# buffNlvlshifter2.net
KiCad netlist of a schematic drawn in Altium Designer
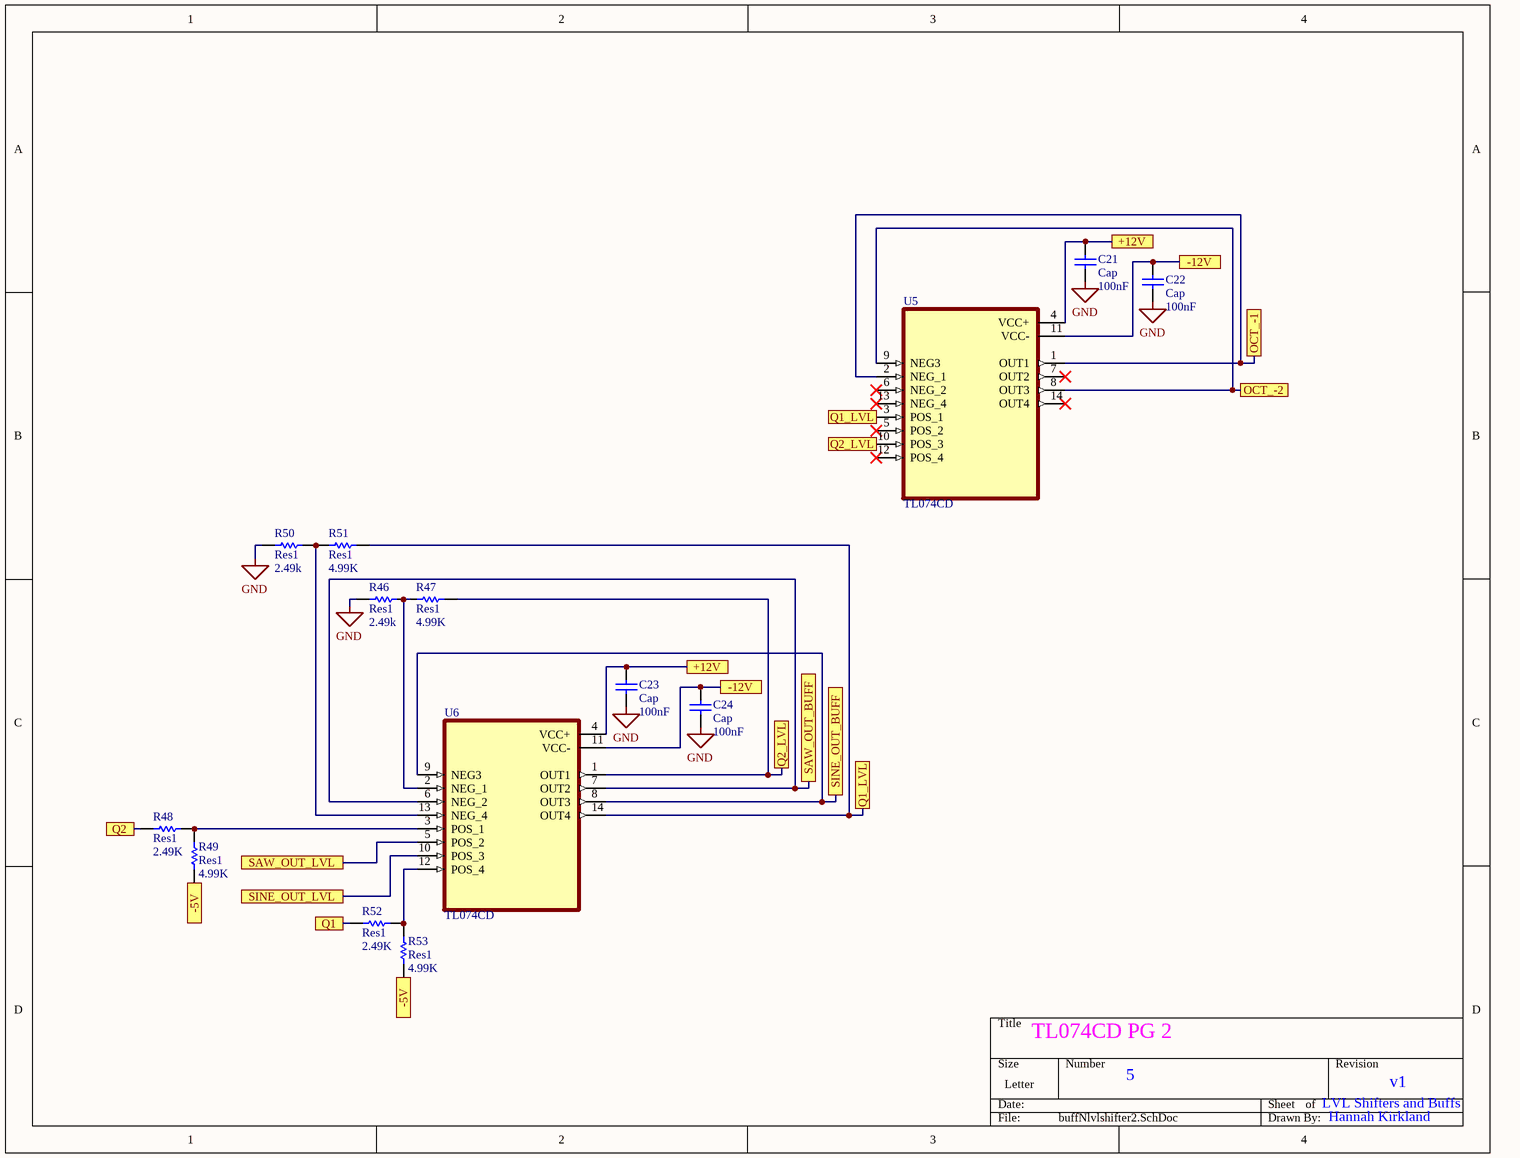
[diagram p0: buffNlvlshifter2.SchDoc]

(export (version "E")
  (design (tool "Eeschema 10.0.6"))
  (components
    (comp (ref "C21")
      (value "Cap")
      (footprint "C1206")
      (description "Capacitor")
      (fields (field (name "ALTIUM_VALUE") "100nF") (field (name "PUBLISHER") "Altium Limited"))
      (libsource (lib "Miscellaneous Devices") (part "Cap"))
    )
    (comp (ref "C22")
      (value "Cap")
      (footprint "C1206")
      (description "Capacitor")
      (fields (field (name "ALTIUM_VALUE") "100nF") (field (name "PUBLISHER") "Altium Limited"))
      (libsource (lib "Miscellaneous Devices") (part "Cap"))
    )
    (comp (ref "C23")
      (value "Cap")
      (footprint "C1206")
      (description "Capacitor")
      (fields (field (name "ALTIUM_VALUE") "100nF") (field (name "PUBLISHER") "Altium Limited"))
      (libsource (lib "Miscellaneous Devices") (part "Cap"))
    )
    (comp (ref "C24")
      (value "Cap")
      (footprint "C1206")
      (description "Capacitor")
      (fields (field (name "ALTIUM_VALUE") "100nF") (field (name "PUBLISHER") "Altium Limited"))
      (libsource (lib "Miscellaneous Devices") (part "Cap"))
    )
    (comp (ref "R46")
      (value "Res1")
      (footprint "C1206")
      (description "Resistor")
      (fields (field (name "ALTIUM_VALUE") "2.49k") (field (name "PUBLISHER") "Altium Limited"))
      (libsource (lib "Miscellaneous Devices") (part "Res1"))
    )
    (comp (ref "R47")
      (value "Res1")
      (footprint "C1206")
      (description "Resistor")
      (fields (field (name "ALTIUM_VALUE") "4.99K") (field (name "PUBLISHER") "Altium Limited"))
      (libsource (lib "Miscellaneous Devices") (part "Res1"))
    )
    (comp (ref "R48")
      (value "Res1")
      (footprint "C1206")
      (description "Resistor")
      (fields (field (name "ALTIUM_VALUE") "2.49K") (field (name "PUBLISHER") "Altium Limited"))
      (libsource (lib "Miscellaneous Devices") (part "Res1"))
    )
    (comp (ref "R49")
      (value "Res1")
      (footprint "C1206")
      (description "Resistor")
      (fields (field (name "ALTIUM_VALUE") "4.99K") (field (name "PUBLISHER") "Altium Limited"))
      (libsource (lib "Miscellaneous Devices") (part "Res1"))
    )
    (comp (ref "R50")
      (value "Res1")
      (footprint "C1206")
      (description "Resistor")
      (fields (field (name "ALTIUM_VALUE") "2.49k") (field (name "PUBLISHER") "Altium Limited"))
      (libsource (lib "Miscellaneous Devices") (part "Res1"))
    )
    (comp (ref "R51")
      (value "Res1")
      (footprint "C1206")
      (description "Resistor")
      (fields (field (name "ALTIUM_VALUE") "4.99K") (field (name "PUBLISHER") "Altium Limited"))
      (libsource (lib "Miscellaneous Devices") (part "Res1"))
    )
    (comp (ref "R52")
      (value "Res1")
      (footprint "C1206")
      (description "Resistor")
      (fields (field (name "ALTIUM_VALUE") "2.49K") (field (name "PUBLISHER") "Altium Limited"))
      (libsource (lib "Miscellaneous Devices") (part "Res1"))
    )
    (comp (ref "R53")
      (value "Res1")
      (footprint "C1206")
      (description "Resistor")
      (fields (field (name "ALTIUM_VALUE") "4.99K") (field (name "PUBLISHER") "Altium Limited"))
      (libsource (lib "Miscellaneous Devices") (part "Res1"))
    )
    (comp (ref "U5")
      (value "TL074CD")
      (footprint "SOIC127P600X175-14N")
      (description "Quad Low-Noise JFET-Input General-Purpose Operational Amplifier 14-SOIC 0 to 70")
      (fields
        (field (name "MF") "Texas Instruments")
        (field (name "BUYPART") "https://www.snapeda.com/parts/TL074CD/Texas%20Instruments/view-part/4793449/?ref=eda")
      )
      (libsource (lib "TL074CD") (part "TL074CD"))
    )
    (comp (ref "U6")
      (value "TL074CD")
      (footprint "SOIC127P600X175-14N")
      (description "Quad Low-Noise JFET-Input General-Purpose Operational Amplifier 14-SOIC 0 to 70")
      (fields
        (field (name "MF") "Texas Instruments")
        (field (name "BUYPART") "https://www.snapeda.com/parts/TL074CD/Texas%20Instruments/view-part/4793449/?ref=eda")
      )
      (libsource (lib "TL074CD") (part "TL074CD"))
    )
  )
  (nets
    (net (code "1") (name "/+12V") (class "Default")
      (node (ref "C21") (pin "2") (pinfunction "2_2") (pintype "passive"))
      (node (ref "C23") (pin "2") (pinfunction "2_2") (pintype "passive"))
      (node (ref "U5") (pin "4") (pinfunction "VCC+_4") (pintype "power_in"))
      (node (ref "U6") (pin "4") (pinfunction "VCC+_4") (pintype "power_in"))
    )
    (net (code "2") (name "/-5V") (class "Default")
      (node (ref "R49") (pin "1") (pinfunction "1_1") (pintype "passive"))
      (node (ref "R53") (pin "1") (pinfunction "1_1") (pintype "passive"))
    )
    (net (code "3") (name "/-12V") (class "Default")
      (node (ref "C22") (pin "2") (pinfunction "2_2") (pintype "passive"))
      (node (ref "C24") (pin "2") (pinfunction "2_2") (pintype "passive"))
      (node (ref "U5") (pin "11") (pinfunction "VCC-_11") (pintype "power_in"))
      (node (ref "U6") (pin "11") (pinfunction "VCC-_11") (pintype "power_in"))
    )
    (net (code "4") (name "/OCT_-1") (class "Default")
      (node (ref "U5") (pin "1") (pinfunction "OUT1_1") (pintype "output"))
      (node (ref "U5") (pin "2") (pinfunction "NEG_1_2") (pintype "input"))
    )
    (net (code "5") (name "/OCT_-2") (class "Default")
      (node (ref "U5") (pin "8") (pinfunction "OUT3_8") (pintype "output"))
      (node (ref "U5") (pin "9") (pinfunction "NEG3_9") (pintype "input"))
    )
    (net (code "6") (name "/Q1") (class "Default")
      (node (ref "R52") (pin "1") (pinfunction "1_1") (pintype "passive"))
    )
    (net (code "7") (name "/Q1_LVL") (class "Default")
      (node (ref "R51") (pin "2") (pinfunction "2_2") (pintype "passive"))
      (node (ref "U5") (pin "3") (pinfunction "POS_1_3") (pintype "input"))
      (node (ref "U6") (pin "14") (pinfunction "OUT4_14") (pintype "output"))
    )
    (net (code "8") (name "/Q2") (class "Default")
      (node (ref "R48") (pin "1") (pinfunction "1_1") (pintype "passive"))
    )
    (net (code "9") (name "/Q2_LVL") (class "Default")
      (node (ref "R47") (pin "2") (pinfunction "2_2") (pintype "passive"))
      (node (ref "U5") (pin "10") (pinfunction "POS_3_10") (pintype "input"))
      (node (ref "U6") (pin "1") (pinfunction "OUT1_1") (pintype "output"))
    )
    (net (code "10") (name "/SAW_OUT_BUFF") (class "Default")
      (node (ref "U6") (pin "6") (pinfunction "NEG_2_6") (pintype "input"))
      (node (ref "U6") (pin "7") (pinfunction "OUT2_7") (pintype "output"))
    )
    (net (code "11") (name "/SAW_OUT_LVL") (class "Default")
      (node (ref "U6") (pin "5") (pinfunction "POS_2_5") (pintype "input"))
    )
    (net (code "12") (name "/SINE_OUT_BUFF") (class "Default")
      (node (ref "U6") (pin "8") (pinfunction "OUT3_8") (pintype "output"))
      (node (ref "U6") (pin "9") (pinfunction "NEG3_9") (pintype "input"))
    )
    (net (code "13") (name "/SINE_OUT_LVL") (class "Default")
      (node (ref "U6") (pin "10") (pinfunction "POS_3_10") (pintype "input"))
    )
    (net (code "14") (name "GND") (class "Default")
      (node (ref "C21") (pin "1") (pinfunction "1_1") (pintype "passive"))
      (node (ref "C22") (pin "1") (pinfunction "1_1") (pintype "passive"))
      (node (ref "C23") (pin "1") (pinfunction "1_1") (pintype "passive"))
      (node (ref "C24") (pin "1") (pinfunction "1_1") (pintype "passive"))
      (node (ref "R46") (pin "1") (pinfunction "1_1") (pintype "passive"))
      (node (ref "R50") (pin "1") (pinfunction "1_1") (pintype "passive"))
    )
    (net (code "15") (name "Net-(U6-NEG_1)") (class "Default")
      (node (ref "R46") (pin "2") (pinfunction "2_2") (pintype "passive"))
      (node (ref "R47") (pin "1") (pinfunction "1_1") (pintype "passive"))
      (node (ref "U6") (pin "2") (pinfunction "NEG_1_2") (pintype "input"))
    )
    (net (code "16") (name "Net-(U6-NEG_4)") (class "Default")
      (node (ref "R50") (pin "2") (pinfunction "2_2") (pintype "passive"))
      (node (ref "R51") (pin "1") (pinfunction "1_1") (pintype "passive"))
      (node (ref "U6") (pin "13") (pinfunction "NEG_4_13") (pintype "input"))
    )
    (net (code "17") (name "Net-(U6-POS_1)") (class "Default")
      (node (ref "R48") (pin "2") (pinfunction "2_2") (pintype "passive"))
      (node (ref "R49") (pin "2") (pinfunction "2_2") (pintype "passive"))
      (node (ref "U6") (pin "3") (pinfunction "POS_1_3") (pintype "input"))
    )
    (net (code "18") (name "Net-(U6-POS_4)") (class "Default")
      (node (ref "R52") (pin "2") (pinfunction "2_2") (pintype "passive"))
      (node (ref "R53") (pin "2") (pinfunction "2_2") (pintype "passive"))
      (node (ref "U6") (pin "12") (pinfunction "POS_4_12") (pintype "input"))
    )
    (net (code "19") (name "unconnected-(U5-NEG_2-Pad6)") (class "Default")
      (node (ref "U5") (pin "6") (pinfunction "NEG_2_6") (pintype "input+no_connect"))
    )
    (net (code "20") (name "unconnected-(U5-NEG_4-Pad13)") (class "Default")
      (node (ref "U5") (pin "13") (pinfunction "NEG_4_13") (pintype "input+no_connect"))
    )
    (net (code "21") (name "unconnected-(U5-OUT2-Pad7)") (class "Default")
      (node (ref "U5") (pin "7") (pinfunction "OUT2_7") (pintype "output+no_connect"))
    )
    (net (code "22") (name "unconnected-(U5-OUT4-Pad14)") (class "Default")
      (node (ref "U5") (pin "14") (pinfunction "OUT4_14") (pintype "output+no_connect"))
    )
    (net (code "23") (name "unconnected-(U5-POS_2-Pad5)") (class "Default")
      (node (ref "U5") (pin "5") (pinfunction "POS_2_5") (pintype "input+no_connect"))
    )
    (net (code "24") (name "unconnected-(U5-POS_4-Pad12)") (class "Default")
      (node (ref "U5") (pin "12") (pinfunction "POS_4_12") (pintype "input+no_connect"))
    )
  )
)
